# board.net
KiCad netlist of a schematic drawn in EAGLE
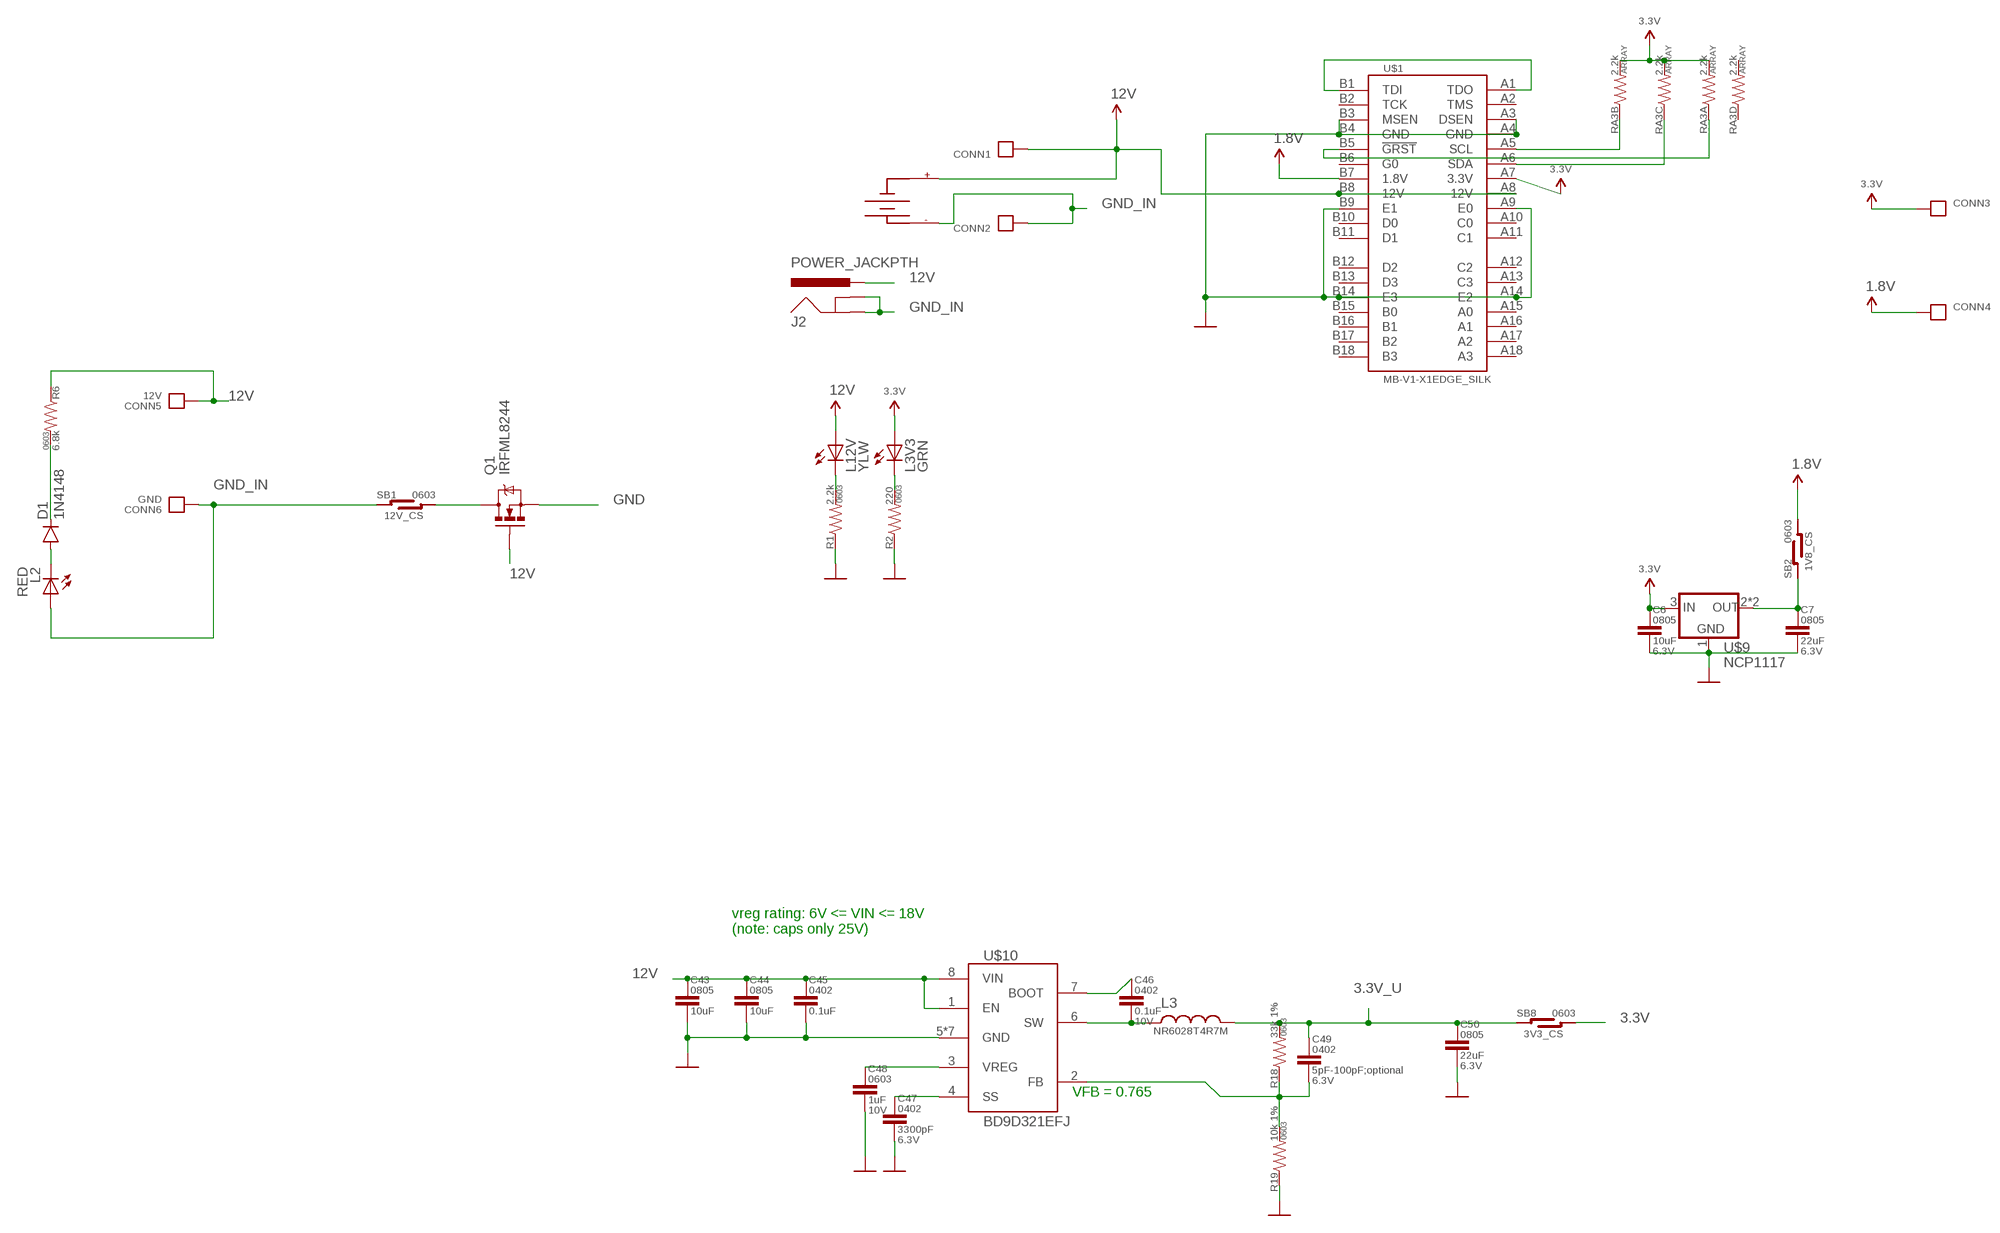
[diagram p0: schematic, sheet 1]

(export (version "E")
  (design (tool "Eeschema 10.0.6"))
  (components
    (comp (ref "C6")
      (value "10uF")
      (footprint "eagle-import:0805-CAP")
      (fields (field (name "VOLTAGE") "6.3V"))
      (libsource (lib "eagle-import") (part "CAP0805"))
    )
    (comp (ref "C7")
      (value "22uF")
      (footprint "eagle-import:0805-CAP")
      (fields (field (name "VOLTAGE") "6.3V"))
      (libsource (lib "eagle-import") (part "CAP0805"))
    )
    (comp (ref "C43")
      (value "10uF")
      (footprint "eagle-import:0805-CAP")
      (fields (field (name "VOLTAGE") "6.3V") (field (name "VOLTAGE_1") "25V"))
      (libsource (lib "eagle-import") (part "CAP0805"))
    )
    (comp (ref "C44")
      (value "10uF")
      (footprint "eagle-import:0805-CAP")
      (fields (field (name "VOLTAGE") "6.3V") (field (name "VOLTAGE_1") "25V"))
      (libsource (lib "eagle-import") (part "CAP0805"))
    )
    (comp (ref "C45")
      (value "0.1uF")
      (footprint "eagle-import:0402-CAP")
      (fields (field (name "VOLTAGE") "6.3V") (field (name "VOLTAGE_1") "25V"))
      (libsource (lib "eagle-import") (part "CAP0402-CAP"))
    )
    (comp (ref "C46")
      (value "0.1uF")
      (footprint "eagle-import:0402-CAP")
      (fields (field (name "VOLTAGE") "6.3V") (field (name "VOLTAGE_1") "10V"))
      (libsource (lib "eagle-import") (part "CAP0402-CAP"))
    )
    (comp (ref "C47")
      (value "3300pF")
      (footprint "eagle-import:0402-CAP")
      (fields (field (name "VOLTAGE") "6.3V"))
      (libsource (lib "eagle-import") (part "CAP0402-CAP"))
    )
    (comp (ref "C48")
      (value "1uF")
      (footprint "eagle-import:0603-CAP")
      (fields (field (name "VOLTAGE") "6.3V") (field (name "VOLTAGE_1") "10V"))
      (libsource (lib "eagle-import") (part "CAP0603"))
    )
    (comp (ref "C49")
      (value "5pF-100pF;optional")
      (footprint "eagle-import:0402-CAP")
      (fields (field (name "VOLTAGE") "6.3V"))
      (libsource (lib "eagle-import") (part "CAP0402-CAP"))
    )
    (comp (ref "C50")
      (value "22uF")
      (footprint "eagle-import:0805-CAP")
      (fields (field (name "VOLTAGE") "6.3V"))
      (libsource (lib "eagle-import") (part "CAP0805"))
    )
    (comp (ref "CONN1")
      (value "CONNECTOR18AWG")
      (footprint "eagle-import:HOLE_18AWG")
      (libsource (lib "eagle-import") (part "CONNECTOR18AWG"))
    )
    (comp (ref "CONN2")
      (value "CONNECTOR18AWG")
      (footprint "eagle-import:HOLE_18AWG")
      (libsource (lib "eagle-import") (part "CONNECTOR18AWG"))
    )
    (comp (ref "CONN3")
      (value "CONNECTOR18AWG")
      (footprint "eagle-import:HOLE_18AWG")
      (libsource (lib "eagle-import") (part "CONNECTOR18AWG"))
    )
    (comp (ref "CONN4")
      (value "CONNECTOR18AWG")
      (footprint "eagle-import:HOLE_18AWG")
      (libsource (lib "eagle-import") (part "CONNECTOR18AWG"))
    )
    (comp (ref "CONN5")
      (value "12V")
      (footprint "eagle-import:SCREW_2.5MM")
      (libsource (lib "eagle-import") (part "CONNECTORSCREW_2.5MM"))
    )
    (comp (ref "CONN6")
      (value "GND")
      (footprint "eagle-import:SCREW_2.5MM")
      (libsource (lib "eagle-import") (part "CONNECTORSCREW_2.5MM"))
    )
    (comp (ref "D1")
      (value "1N4148")
      (footprint "eagle-import:SOD-323")
      (libsource (lib "eagle-import") (part "DIODESOD"))
    )
    (comp (ref "J2")
      (value "POWER_JACKPTH")
      (footprint "eagle-import:POWER_JACK_PTH")
      (libsource (lib "eagle-import") (part "POWER_JACKPTH"))
    )
    (comp (ref "L2")
      (value "RED")
      (footprint "eagle-import:0603_LED")
      (libsource (lib "eagle-import") (part "LED0603"))
    )
    (comp (ref "L3")
      (value "NR6028T4R7M")
      (footprint "eagle-import:NR60XX")
      (libsource (lib "eagle-import") (part "INDUCTORNR60XX"))
    )
    (comp (ref "L3V3")
      (value "GRN")
      (footprint "eagle-import:0603_LED")
      (libsource (lib "eagle-import") (part "LED0603"))
    )
    (comp (ref "L12V")
      (value "YLW")
      (footprint "eagle-import:0603_LED")
      (libsource (lib "eagle-import") (part "LED0603"))
    )
    (comp (ref "Q1")
      (value "IRFML8244")
      (footprint "eagle-import:SOT23")
      (libsource (lib "eagle-import") (part "MOSFET-NCHANNELBSS138"))
    )
    (comp (ref "R1")
      (value "2.2k")
      (footprint "eagle-import:0603-RES")
      (libsource (lib "eagle-import") (part "RESISTOR0603"))
    )
    (comp (ref "R2")
      (value "220")
      (footprint "eagle-import:0603-RES")
      (libsource (lib "eagle-import") (part "RESISTOR0603"))
    )
    (comp (ref "R6")
      (value "6.8k")
      (footprint "eagle-import:0603-RES")
      (libsource (lib "eagle-import") (part "RESISTOR0603"))
    )
    (comp (ref "R18")
      (value "33k 1%")
      (footprint "eagle-import:0603-RES")
      (libsource (lib "eagle-import") (part "RESISTOR0603"))
    )
    (comp (ref "R19")
      (value "10k 1%")
      (footprint "eagle-import:0603-RES")
      (libsource (lib "eagle-import") (part "RESISTOR0603"))
    )
    (comp (ref "RA3")
      (value "2.2k")
      (footprint "eagle-import:0603-ARV")
      (libsource (lib "eagle-import") (part "RESISTOR_ARRAY0603_X4"))
    )
    (comp (ref "SB1")
      (value "12V_CS")
      (footprint "eagle-import:SB-0603")
      (libsource (lib "eagle-import") (part "SOLDER-BRIDGE0603"))
    )
    (comp (ref "SB2")
      (value "1V8_CS")
      (footprint "eagle-import:SB-0603")
      (libsource (lib "eagle-import") (part "SOLDER-BRIDGE0603"))
    )
    (comp (ref "SB8")
      (value "3V3_CS")
      (footprint "eagle-import:SB-0603")
      (libsource (lib "eagle-import") (part "SOLDER-BRIDGE0603"))
    )
    (comp (ref "U$1")
      (value "MB-V1-X1EDGE_SILK")
      (footprint "eagle-import:MB-V1-X1-EDGE")
      (libsource (lib "eagle-import") (part "MB-V1-X1EDGE_SILK"))
    )
    (comp (ref "U$4")
      (value "SUPPLYPCIE-6-RA")
      (footprint "eagle-import:MOLEX_MINIFITJR_6_RA")
      (libsource (lib "eagle-import") (part "SUPPLYPCIE-6-RA"))
    )
    (comp (ref "U$9")
      (value "NCP1117")
      (footprint "eagle-import:SOT223")
      (libsource (lib "eagle-import") (part "VREGSOT223"))
    )
    (comp (ref "U$10")
      (value "BD9D321EFJ")
      (footprint "eagle-import:HTSOP8")
      (libsource (lib "eagle-import") (part "BD9D321EFJ"))
    )
  )
  (nets
    (net (code "1") (name "/3.3V_U") (class "Default")
      (node (ref "C49") (pin "1") (pinfunction "1_1") (pintype "passive"))
      (node (ref "C50") (pin "1") (pinfunction "1_1") (pintype "passive"))
      (node (ref "L3") (pin "P$2") (pinfunction "2_P$2") (pintype "passive"))
      (node (ref "R18") (pin "2") (pinfunction "2_2") (pintype "passive"))
      (node (ref "SB8") (pin "L1") (pinfunction "P$1_L1") (pintype "passive"))
      (node (ref "SB8") (pin "L2") (pinfunction "P$1_L2") (pintype "passive"))
    )
    (net (code "2") (name "/GND_IN") (class "Default")
      (node (ref "CONN2") (pin "P$1") (pinfunction "P_P$1") (pintype "bidirectional"))
      (node (ref "CONN6") (pin "P") (pinfunction "P_P") (pintype "bidirectional"))
      (node (ref "J2") (pin "GND") (pinfunction "GND_GND") (pintype "bidirectional"))
      (node (ref "J2") (pin "GNDBREAK") (pinfunction "GNDBREAK_GNDBREAK") (pintype "bidirectional"))
      (node (ref "L2") (pin "A") (pinfunction "A_A") (pintype "passive"))
      (node (ref "SB1") (pin "L1") (pinfunction "P$1_L1") (pintype "passive"))
      (node (ref "SB1") (pin "L2") (pinfunction "P$1_L2") (pintype "passive"))
      (node (ref "U$4") (pin "4") (pinfunction "GND_4") (pintype "bidirectional"))
      (node (ref "U$4") (pin "6") (pinfunction "GND_6") (pintype "bidirectional"))
    )
    (net (code "3") (name "1.8V") (class "Default")
      (node (ref "CONN4") (pin "P$1") (pinfunction "P_P$1") (pintype "bidirectional"))
      (node (ref "SB2") (pin "R1") (pinfunction "P$2_R1") (pintype "passive"))
      (node (ref "SB2") (pin "R2") (pinfunction "P$2_R2") (pintype "passive"))
      (node (ref "U$1") (pin "B7") (pinfunction "1.8V_B7") (pintype "bidirectional"))
    )
    (net (code "4") (name "3.3V") (class "Default")
      (node (ref "C6") (pin "1") (pinfunction "1_1") (pintype "passive"))
      (node (ref "CONN3") (pin "P$1") (pinfunction "P_P$1") (pintype "bidirectional"))
      (node (ref "L3V3") (pin "A") (pinfunction "A_A") (pintype "passive"))
      (node (ref "RA3") (pin "6") (pinfunction "2_6") (pintype "passive"))
      (node (ref "RA3") (pin "7") (pinfunction "2_7") (pintype "passive"))
      (node (ref "RA3") (pin "8") (pinfunction "2_8") (pintype "passive"))
      (node (ref "SB8") (pin "R1") (pinfunction "P$2_R1") (pintype "passive"))
      (node (ref "SB8") (pin "R2") (pinfunction "P$2_R2") (pintype "passive"))
      (node (ref "U$1") (pin "A7") (pinfunction "3.3V_A7") (pintype "bidirectional"))
      (node (ref "U$9") (pin "3") (pinfunction "IN_3") (pintype "input"))
    )
    (net (code "5") (name "12V") (class "Default")
      (node (ref "C43") (pin "1") (pinfunction "1_1") (pintype "passive"))
      (node (ref "C44") (pin "1") (pinfunction "1_1") (pintype "passive"))
      (node (ref "C45") (pin "1") (pinfunction "1_1") (pintype "passive"))
      (node (ref "CONN1") (pin "P$1") (pinfunction "P_P$1") (pintype "bidirectional"))
      (node (ref "CONN5") (pin "P") (pinfunction "P_P") (pintype "bidirectional"))
      (node (ref "J2") (pin "PWR") (pinfunction "PWR_PWR") (pintype "bidirectional"))
      (node (ref "L12V") (pin "A") (pinfunction "A_A") (pintype "passive"))
      (node (ref "Q1") (pin "1") (pinfunction "G_1") (pintype "passive"))
      (node (ref "R6") (pin "1") (pinfunction "1_1") (pintype "passive"))
      (node (ref "U$1") (pin "A8") (pinfunction "12V_A8") (pintype "bidirectional"))
      (node (ref "U$1") (pin "B8") (pinfunction "12V_B8") (pintype "bidirectional"))
      (node (ref "U$10") (pin "1") (pinfunction "EN_1") (pintype "input"))
      (node (ref "U$10") (pin "8") (pinfunction "VIN_8") (pintype "input"))
      (node (ref "U$4") (pin "1") (pinfunction "VSUPPLY_1") (pintype "bidirectional"))
      (node (ref "U$4") (pin "3") (pinfunction "VSUPPLY_3") (pintype "bidirectional"))
    )
    (net (code "6") (name "GND") (class "Default")
      (node (ref "C43") (pin "2") (pinfunction "2_2") (pintype "passive"))
      (node (ref "C44") (pin "2") (pinfunction "2_2") (pintype "passive"))
      (node (ref "C45") (pin "2") (pinfunction "2_2") (pintype "passive"))
      (node (ref "C47") (pin "2") (pinfunction "2_2") (pintype "passive"))
      (node (ref "C48") (pin "2") (pinfunction "2_2") (pintype "passive"))
      (node (ref "C50") (pin "2") (pinfunction "2_2") (pintype "passive"))
      (node (ref "C6") (pin "2") (pinfunction "2_2") (pintype "passive"))
      (node (ref "C7") (pin "2") (pinfunction "2_2") (pintype "passive"))
      (node (ref "Q1") (pin "2") (pinfunction "S_2") (pintype "passive"))
      (node (ref "R1") (pin "1") (pinfunction "1_1") (pintype "passive"))
      (node (ref "R19") (pin "1") (pinfunction "1_1") (pintype "passive"))
      (node (ref "R2") (pin "1") (pinfunction "1_1") (pintype "passive"))
      (node (ref "U$1") (pin "A14") (pinfunction "E2_A14") (pintype "bidirectional"))
      (node (ref "U$1") (pin "A3") (pinfunction "DSEN_A3") (pintype "bidirectional"))
      (node (ref "U$1") (pin "A4") (pinfunction "GND_A4") (pintype "input"))
      (node (ref "U$1") (pin "A9") (pinfunction "E0_A9") (pintype "bidirectional"))
      (node (ref "U$1") (pin "B14") (pinfunction "E3_B14") (pintype "bidirectional"))
      (node (ref "U$1") (pin "B3") (pinfunction "MSEN_B3") (pintype "bidirectional"))
      (node (ref "U$1") (pin "B4") (pinfunction "GND_B4") (pintype "input"))
      (node (ref "U$1") (pin "B9") (pinfunction "E1_B9") (pintype "bidirectional"))
      (node (ref "U$10") (pin "5") (pinfunction "GND_5") (pintype "input"))
      (node (ref "U$10") (pin "P$1") (pinfunction "GND_P$1") (pintype "input"))
      (node (ref "U$10") (pin "P$2") (pinfunction "GND_P$2") (pintype "input"))
      (node (ref "U$10") (pin "P$3") (pinfunction "GND_P$3") (pintype "input"))
      (node (ref "U$10") (pin "P$4") (pinfunction "GND_P$4") (pintype "input"))
      (node (ref "U$10") (pin "P$5") (pinfunction "GND_P$5") (pintype "input"))
      (node (ref "U$10") (pin "PAD") (pinfunction "GND_PAD") (pintype "input"))
      (node (ref "U$9") (pin "1") (pinfunction "GND_1") (pintype "input"))
    )
    (net (code "7") (name "Net-(C7-Pad1)") (class "Default")
      (node (ref "C7") (pin "1") (pinfunction "1_1") (pintype "passive"))
      (node (ref "SB2") (pin "L1") (pinfunction "P$1_L1") (pintype "passive"))
      (node (ref "SB2") (pin "L2") (pinfunction "P$1_L2") (pintype "passive"))
      (node (ref "U$9") (pin "2") (pinfunction "OUT_2") (pintype "passive"))
      (node (ref "U$9") (pin "4") (pinfunction "OUT_4") (pintype "passive"))
    )
    (net (code "8") (name "Net-(D1-PadA)") (class "Default")
      (node (ref "D1") (pin "A") (pinfunction "A_A") (pintype "passive"))
      (node (ref "L2") (pin "C") (pinfunction "C_C") (pintype "passive"))
    )
    (net (code "9") (name "Net-(D1-PadC)") (class "Default")
      (node (ref "D1") (pin "C") (pinfunction "C_C") (pintype "passive"))
      (node (ref "R6") (pin "2") (pinfunction "2_2") (pintype "passive"))
    )
    (net (code "10") (name "Net-(L3-1)") (class "Default")
      (node (ref "C46") (pin "2") (pinfunction "2_2") (pintype "passive"))
      (node (ref "L3") (pin "P$1") (pinfunction "1_P$1") (pintype "passive"))
      (node (ref "U$10") (pin "6") (pinfunction "SW_6") (pintype "input"))
    )
    (net (code "11") (name "Net-(L3V3-PadC)") (class "Default")
      (node (ref "L3V3") (pin "C") (pinfunction "C_C") (pintype "passive"))
      (node (ref "R2") (pin "2") (pinfunction "2_2") (pintype "passive"))
    )
    (net (code "12") (name "Net-(L12V-PadC)") (class "Default")
      (node (ref "L12V") (pin "C") (pinfunction "C_C") (pintype "passive"))
      (node (ref "R1") (pin "2") (pinfunction "2_2") (pintype "passive"))
    )
    (net (code "13") (name "Net-(Q1-D)") (class "Default")
      (node (ref "Q1") (pin "3") (pinfunction "D_3") (pintype "passive"))
      (node (ref "SB1") (pin "R1") (pinfunction "P$2_R1") (pintype "passive"))
      (node (ref "SB1") (pin "R2") (pinfunction "P$2_R2") (pintype "passive"))
    )
    (net (code "14") (name "Net-(RA3B-1)") (class "Default")
      (node (ref "RA3") (pin "2") (pinfunction "1_2") (pintype "passive"))
      (node (ref "U$1") (pin "A5") (pinfunction "SCL_A5") (pintype "bidirectional"))
    )
    (net (code "15") (name "Net-(RA3C-1)") (class "Default")
      (node (ref "RA3") (pin "3") (pinfunction "1_3") (pintype "passive"))
      (node (ref "U$1") (pin "A6") (pinfunction "SDA_A6") (pintype "bidirectional"))
    )
    (net (code "16") (name "Net-(U$1-TDI)") (class "Default")
      (node (ref "U$1") (pin "A1") (pinfunction "TDO_A1") (pintype "bidirectional"))
      (node (ref "U$1") (pin "B1") (pinfunction "TDI_B1") (pintype "bidirectional"))
    )
    (net (code "17") (name "Net-(U$1-~{GRST})") (class "Default")
      (node (ref "RA3") (pin "1") (pinfunction "1_1") (pintype "passive"))
      (node (ref "U$1") (pin "B5") (pinfunction "~{GRST}_B5") (pintype "bidirectional"))
    )
    (net (code "18") (name "Net-(U$10-BOOT)") (class "Default")
      (node (ref "C46") (pin "1") (pinfunction "1_1") (pintype "passive"))
      (node (ref "U$10") (pin "7") (pinfunction "BOOT_7") (pintype "input"))
    )
    (net (code "19") (name "Net-(U$10-FB)") (class "Default")
      (node (ref "C49") (pin "2") (pinfunction "2_2") (pintype "passive"))
      (node (ref "R18") (pin "1") (pinfunction "1_1") (pintype "passive"))
      (node (ref "R19") (pin "2") (pinfunction "2_2") (pintype "passive"))
      (node (ref "U$10") (pin "2") (pinfunction "FB_2") (pintype "input"))
    )
    (net (code "20") (name "Net-(U$10-SS)") (class "Default")
      (node (ref "C47") (pin "1") (pinfunction "1_1") (pintype "passive"))
      (node (ref "U$10") (pin "4") (pinfunction "SS_4") (pintype "input"))
    )
    (net (code "21") (name "Net-(U$10-VREG)") (class "Default")
      (node (ref "C48") (pin "1") (pinfunction "1_1") (pintype "passive"))
      (node (ref "U$10") (pin "3") (pinfunction "VREG_3") (pintype "input"))
    )
    (net (code "22") (name "unconnected-(RA3D-1-Pad4)") (class "Default")
      (node (ref "RA3") (pin "4") (pinfunction "1_4") (pintype "passive"))
    )
    (net (code "23") (name "unconnected-(RA3D-2-Pad5)") (class "Default")
      (node (ref "RA3") (pin "5") (pinfunction "2_5") (pintype "passive"))
    )
    (net (code "24") (name "unconnected-(U$1-A0-PadA15)") (class "Default")
      (node (ref "U$1") (pin "A15") (pinfunction "A0_A15") (pintype "bidirectional"))
    )
    (net (code "25") (name "unconnected-(U$1-A1-PadA16)") (class "Default")
      (node (ref "U$1") (pin "A16") (pinfunction "A1_A16") (pintype "bidirectional"))
    )
    (net (code "26") (name "unconnected-(U$1-A2-PadA17)") (class "Default")
      (node (ref "U$1") (pin "A17") (pinfunction "A2_A17") (pintype "bidirectional"))
    )
    (net (code "27") (name "unconnected-(U$1-A3-PadA18)") (class "Default")
      (node (ref "U$1") (pin "A18") (pinfunction "A3_A18") (pintype "bidirectional"))
    )
    (net (code "28") (name "unconnected-(U$1-B0-PadB15)") (class "Default")
      (node (ref "U$1") (pin "B15") (pinfunction "B0_B15") (pintype "bidirectional"))
    )
    (net (code "29") (name "unconnected-(U$1-B1-PadB16)") (class "Default")
      (node (ref "U$1") (pin "B16") (pinfunction "B1_B16") (pintype "bidirectional"))
    )
    (net (code "30") (name "unconnected-(U$1-B2-PadB17)") (class "Default")
      (node (ref "U$1") (pin "B17") (pinfunction "B2_B17") (pintype "bidirectional"))
    )
    (net (code "31") (name "unconnected-(U$1-B3-PadB18)") (class "Default")
      (node (ref "U$1") (pin "B18") (pinfunction "B3_B18") (pintype "bidirectional"))
    )
    (net (code "32") (name "unconnected-(U$1-C0-PadA10)") (class "Default")
      (node (ref "U$1") (pin "A10") (pinfunction "C0_A10") (pintype "bidirectional"))
    )
    (net (code "33") (name "unconnected-(U$1-C1-PadA11)") (class "Default")
      (node (ref "U$1") (pin "A11") (pinfunction "C1_A11") (pintype "bidirectional"))
    )
    (net (code "34") (name "unconnected-(U$1-C2-PadA12)") (class "Default")
      (node (ref "U$1") (pin "A12") (pinfunction "C2_A12") (pintype "bidirectional"))
    )
    (net (code "35") (name "unconnected-(U$1-C3-PadA13)") (class "Default")
      (node (ref "U$1") (pin "A13") (pinfunction "C3_A13") (pintype "bidirectional"))
    )
    (net (code "36") (name "unconnected-(U$1-D0-PadB10)") (class "Default")
      (node (ref "U$1") (pin "B10") (pinfunction "D0_B10") (pintype "bidirectional"))
    )
    (net (code "37") (name "unconnected-(U$1-D1-PadB11)") (class "Default")
      (node (ref "U$1") (pin "B11") (pinfunction "D1_B11") (pintype "bidirectional"))
    )
    (net (code "38") (name "unconnected-(U$1-D2-PadB12)") (class "Default")
      (node (ref "U$1") (pin "B12") (pinfunction "D2_B12") (pintype "bidirectional"))
    )
    (net (code "39") (name "unconnected-(U$1-D3-PadB13)") (class "Default")
      (node (ref "U$1") (pin "B13") (pinfunction "D3_B13") (pintype "bidirectional"))
    )
    (net (code "40") (name "unconnected-(U$1-G0-PadB6)") (class "Default")
      (node (ref "U$1") (pin "B6") (pinfunction "G0_B6") (pintype "bidirectional"))
    )
    (net (code "41") (name "unconnected-(U$1-TCK-PadB2)") (class "Default")
      (node (ref "U$1") (pin "B2") (pinfunction "TCK_B2") (pintype "bidirectional"))
    )
    (net (code "42") (name "unconnected-(U$1-TMS-PadA2)") (class "Default")
      (node (ref "U$1") (pin "A2") (pinfunction "TMS_A2") (pintype "bidirectional"))
    )
  )
)
